# rony_4_buttons.net
KiCad netlist of a schematic drawn in EAGLE
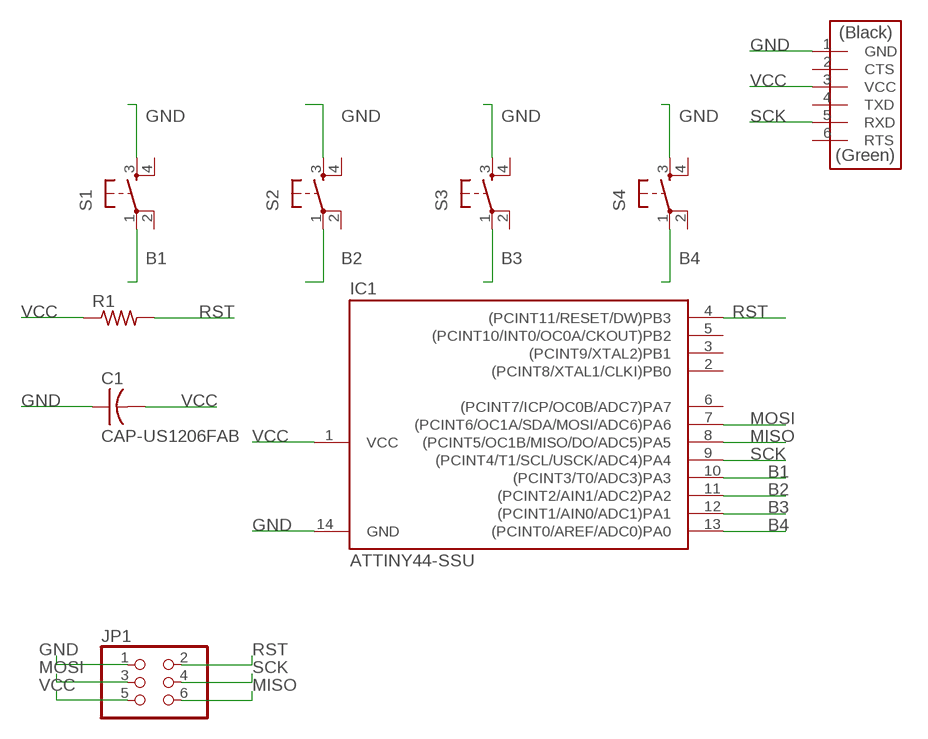
[diagram p0: schematic, sheet 1]

(export (version "E")
  (design (tool "Eeschema 10.0.6"))
  (components
    (comp (ref "C1")
      (value "CAP-US1206FAB")
      (footprint "eagle-import:C1206FAB")
      (libsource (lib "eagle-import") (part "CAP-US1206FAB"))
    )
    (comp (ref "IC1")
      (value "ATTINY44-SSU")
      (footprint "eagle-import:SOIC14")
      (libsource (lib "eagle-import") (part "ATTINY44-SSU"))
    )
    (comp (ref "JP1")
      (value "PINHD-2X3-SMD")
      (footprint "eagle-import:2X03SMD")
      (libsource (lib "eagle-import") (part "PINHD-2X3-SMD"))
    )
    (comp (ref "R1")
      (value "RES-US1206FAB")
      (footprint "eagle-import:R1206FAB")
      (libsource (lib "eagle-import") (part "RES-US1206FAB"))
    )
    (comp (ref "S1")
      (value "6MM_SWITCH6MM_SWITCH")
      (footprint "eagle-import:6MM_SWITCH")
      (libsource (lib "eagle-import") (part "6MM_SWITCH6MM_SWITCH"))
    )
    (comp (ref "S2")
      (value "6MM_SWITCH6MM_SWITCH")
      (footprint "eagle-import:6MM_SWITCH")
      (libsource (lib "eagle-import") (part "6MM_SWITCH6MM_SWITCH"))
    )
    (comp (ref "S3")
      (value "6MM_SWITCH6MM_SWITCH")
      (footprint "eagle-import:6MM_SWITCH")
      (libsource (lib "eagle-import") (part "6MM_SWITCH6MM_SWITCH"))
    )
    (comp (ref "S4")
      (value "6MM_SWITCH6MM_SWITCH")
      (footprint "eagle-import:6MM_SWITCH")
      (libsource (lib "eagle-import") (part "6MM_SWITCH6MM_SWITCH"))
    )
    (comp (ref "U$1")
      (value "FTDI-SMD-HEADER")
      (footprint "eagle-import:1X06SMD")
      (libsource (lib "eagle-import") (part "FTDI-SMD-HEADER"))
    )
  )
  (nets
    (net (code "1") (name "/B1") (class "Default")
      (node (ref "IC1") (pin "10") (pinfunction "(PCINT3/T0/ADC3)PA3_10") (pintype "bidirectional"))
      (node (ref "S1") (pin "1") (pinfunction "P_1") (pintype "passive"))
    )
    (net (code "2") (name "/B2") (class "Default")
      (node (ref "IC1") (pin "11") (pinfunction "(PCINT2/AIN1/ADC2)PA2_11") (pintype "bidirectional"))
      (node (ref "S2") (pin "1") (pinfunction "P_1") (pintype "passive"))
    )
    (net (code "3") (name "/B3") (class "Default")
      (node (ref "IC1") (pin "12") (pinfunction "(PCINT1/AIN0/ADC1)PA1_12") (pintype "bidirectional"))
      (node (ref "S3") (pin "1") (pinfunction "P_1") (pintype "passive"))
    )
    (net (code "4") (name "/B4") (class "Default")
      (node (ref "IC1") (pin "13") (pinfunction "(PCINT0/AREF/ADC0)PA0_13") (pintype "bidirectional"))
      (node (ref "S4") (pin "1") (pinfunction "P_1") (pintype "passive"))
    )
    (net (code "5") (name "/GND") (class "Default")
      (node (ref "C1") (pin "1") (pinfunction "1_1") (pintype "passive"))
      (node (ref "IC1") (pin "14") (pinfunction "GND_14") (pintype "power_in"))
      (node (ref "JP1") (pin "1") (pinfunction "1_1") (pintype "passive"))
      (node (ref "S1") (pin "3") (pinfunction "S_3") (pintype "passive"))
      (node (ref "S2") (pin "3") (pinfunction "S_3") (pintype "passive"))
      (node (ref "S3") (pin "3") (pinfunction "S_3") (pintype "passive"))
      (node (ref "S4") (pin "3") (pinfunction "S_3") (pintype "passive"))
      (node (ref "U$1") (pin "1") (pinfunction "GND_1") (pintype "bidirectional"))
    )
    (net (code "6") (name "/MISO") (class "Default")
      (node (ref "IC1") (pin "8") (pinfunction "(PCINT5/OC1B/MISO/DO/ADC5)PA5_8") (pintype "bidirectional"))
      (node (ref "JP1") (pin "6") (pinfunction "6_6") (pintype "passive"))
    )
    (net (code "7") (name "/MOSI") (class "Default")
      (node (ref "IC1") (pin "7") (pinfunction "(PCINT6/OC1A/SDA/MOSI/ADC6)PA6_7") (pintype "bidirectional"))
      (node (ref "JP1") (pin "3") (pinfunction "3_3") (pintype "passive"))
    )
    (net (code "8") (name "/RST") (class "Default")
      (node (ref "IC1") (pin "4") (pinfunction "(PCINT11/RESET/DW)PB3_4") (pintype "bidirectional"))
      (node (ref "JP1") (pin "2") (pinfunction "2_2") (pintype "passive"))
      (node (ref "R1") (pin "2") (pinfunction "2_2") (pintype "passive"))
    )
    (net (code "9") (name "/SCK") (class "Default")
      (node (ref "IC1") (pin "9") (pinfunction "(PCINT4/T1/SCL/USCK/ADC4)PA4_9") (pintype "bidirectional"))
      (node (ref "JP1") (pin "4") (pinfunction "4_4") (pintype "passive"))
      (node (ref "U$1") (pin "5") (pinfunction "RXD_5") (pintype "bidirectional"))
    )
    (net (code "10") (name "/VCC") (class "Default")
      (node (ref "C1") (pin "2") (pinfunction "2_2") (pintype "passive"))
      (node (ref "IC1") (pin "1") (pinfunction "VCC_1") (pintype "power_in"))
      (node (ref "JP1") (pin "5") (pinfunction "5_5") (pintype "passive"))
      (node (ref "R1") (pin "1") (pinfunction "1_1") (pintype "passive"))
      (node (ref "U$1") (pin "3") (pinfunction "VCC_3") (pintype "bidirectional"))
    )
    (net (code "11") (name "unconnected-(IC1-(PCINT7{slash}ICP{slash}OC0B{slash}ADC7)PA7-Pad6)") (class "Default")
      (node (ref "IC1") (pin "6") (pinfunction "(PCINT7/ICP/OC0B/ADC7)PA7_6") (pintype "bidirectional"))
    )
    (net (code "12") (name "unconnected-(IC1-(PCINT8{slash}XTAL1{slash}CLKI)PB0-Pad2)") (class "Default")
      (node (ref "IC1") (pin "2") (pinfunction "(PCINT8/XTAL1/CLKI)PB0_2") (pintype "bidirectional"))
    )
    (net (code "13") (name "unconnected-(IC1-(PCINT9{slash}XTAL2)PB1-Pad3)") (class "Default")
      (node (ref "IC1") (pin "3") (pinfunction "(PCINT9/XTAL2)PB1_3") (pintype "bidirectional"))
    )
    (net (code "14") (name "unconnected-(IC1-(PCINT10{slash}INT0{slash}OC0A{slash}CKOUT)PB2-Pad5)") (class "Default")
      (node (ref "IC1") (pin "5") (pinfunction "(PCINT10/INT0/OC0A/CKOUT)PB2_5") (pintype "bidirectional"))
    )
    (net (code "15") (name "unconnected-(S1-P1-Pad2)") (class "Default")
      (node (ref "S1") (pin "2") (pinfunction "P1_2") (pintype "passive"))
    )
    (net (code "16") (name "unconnected-(S1-S1-Pad4)") (class "Default")
      (node (ref "S1") (pin "4") (pinfunction "S1_4") (pintype "passive"))
    )
    (net (code "17") (name "unconnected-(S2-P1-Pad2)") (class "Default")
      (node (ref "S2") (pin "2") (pinfunction "P1_2") (pintype "passive"))
    )
    (net (code "18") (name "unconnected-(S2-S1-Pad4)") (class "Default")
      (node (ref "S2") (pin "4") (pinfunction "S1_4") (pintype "passive"))
    )
    (net (code "19") (name "unconnected-(S3-P1-Pad2)") (class "Default")
      (node (ref "S3") (pin "2") (pinfunction "P1_2") (pintype "passive"))
    )
    (net (code "20") (name "unconnected-(S3-S1-Pad4)") (class "Default")
      (node (ref "S3") (pin "4") (pinfunction "S1_4") (pintype "passive"))
    )
    (net (code "21") (name "unconnected-(S4-P1-Pad2)") (class "Default")
      (node (ref "S4") (pin "2") (pinfunction "P1_2") (pintype "passive"))
    )
    (net (code "22") (name "unconnected-(S4-S1-Pad4)") (class "Default")
      (node (ref "S4") (pin "4") (pinfunction "S1_4") (pintype "passive"))
    )
    (net (code "23") (name "unconnected-(U$1-CTS-Pad2)") (class "Default")
      (node (ref "U$1") (pin "2") (pinfunction "CTS_2") (pintype "bidirectional"))
    )
    (net (code "24") (name "unconnected-(U$1-RTS-Pad6)") (class "Default")
      (node (ref "U$1") (pin "6") (pinfunction "RTS_6") (pintype "bidirectional"))
    )
    (net (code "25") (name "unconnected-(U$1-TXD-Pad4)") (class "Default")
      (node (ref "U$1") (pin "4") (pinfunction "TXD_4") (pintype "bidirectional"))
    )
  )
)
